# Digital.net
KiCad netlist of a schematic drawn in Altium Designer
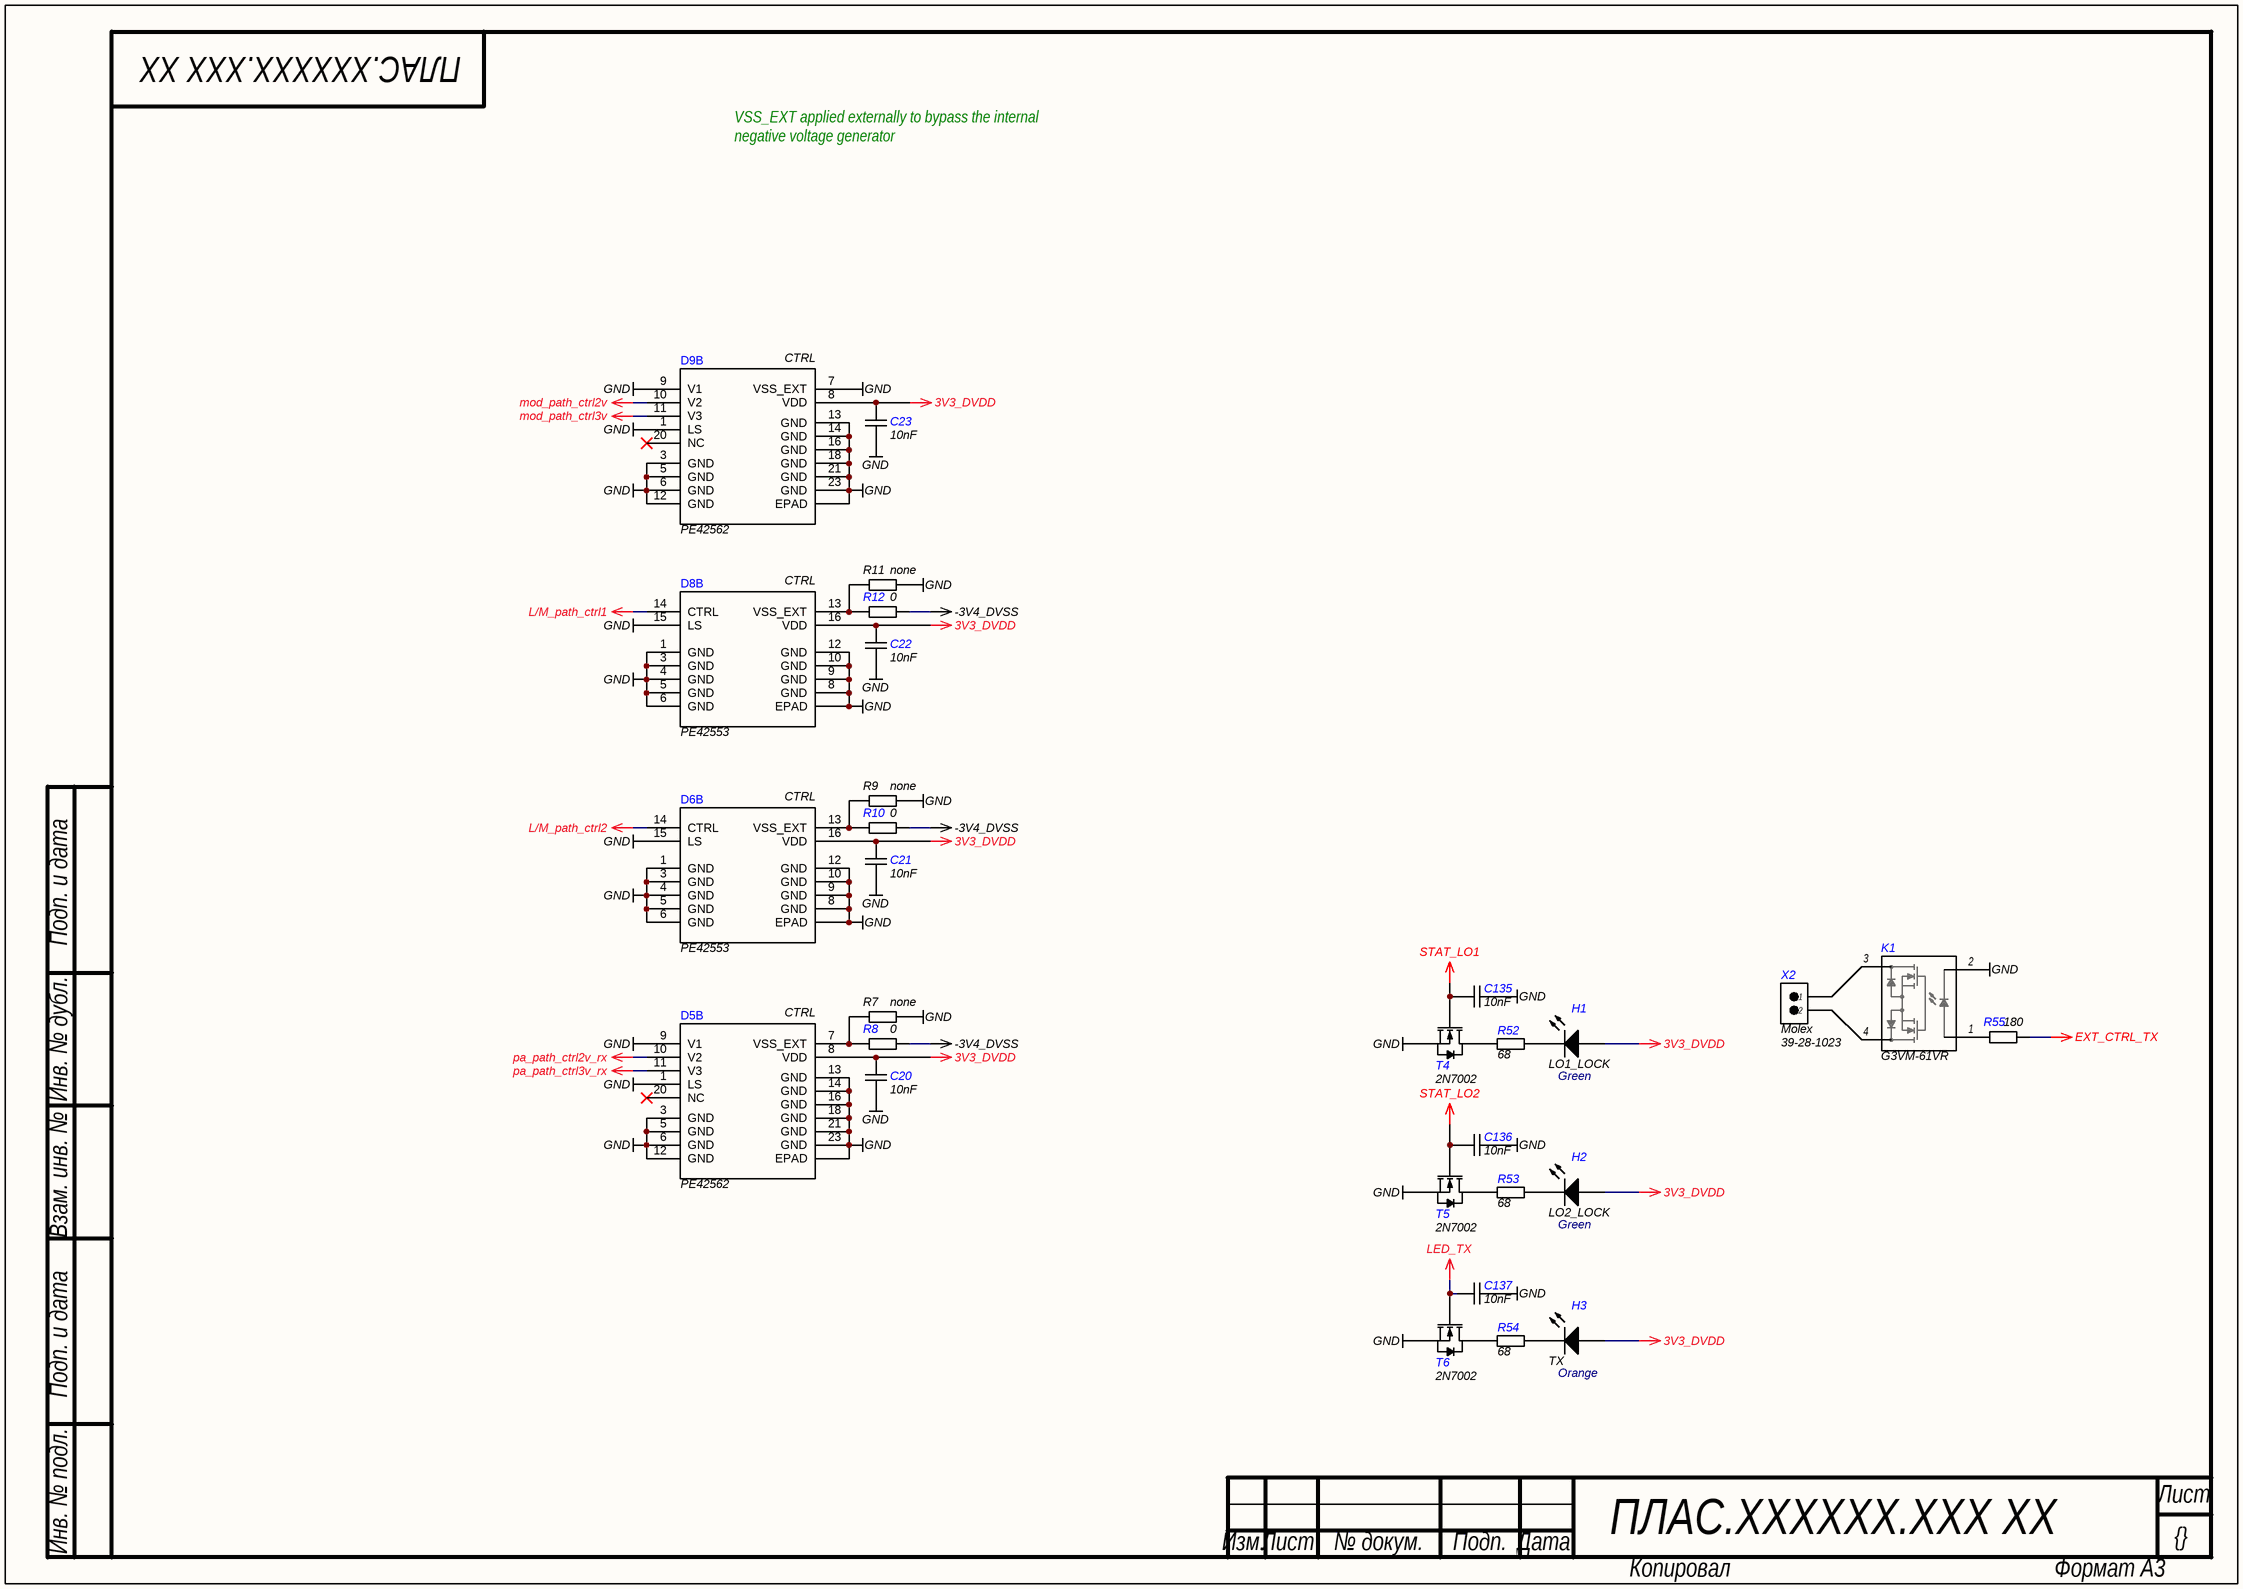
[diagram p0: Digital.SchDoc]

(export (version "E")
  (design (tool "Eeschema 10.0.6"))
  (components
    (comp (ref "C20")
      (value "10nF")
      (footprint "C0402")
      (description "SMD Capacitor")
      (fields (field (name "MANUFACTURER") "Murata") (field (name "TOLERANCE") "10%"))
      (libsource (lib "Kintex_SDR") (part "CAP"))
    )
    (comp (ref "C21")
      (value "10nF")
      (footprint "C0402")
      (description "SMD Capacitor")
      (fields (field (name "MANUFACTURER") "Murata") (field (name "TOLERANCE") "10%"))
      (libsource (lib "Kintex_SDR") (part "CAP"))
    )
    (comp (ref "C22")
      (value "10nF")
      (footprint "C0402")
      (description "SMD Capacitor")
      (fields (field (name "MANUFACTURER") "Murata") (field (name "TOLERANCE") "10%"))
      (libsource (lib "Kintex_SDR") (part "CAP"))
    )
    (comp (ref "C23")
      (value "10nF")
      (footprint "C0402")
      (description "SMD Capacitor")
      (fields (field (name "MANUFACTURER") "Murata") (field (name "TOLERANCE") "10%"))
      (libsource (lib "Kintex_SDR") (part "CAP"))
    )
    (comp (ref "C135")
      (value "10nF")
      (footprint "C0402")
      (description "SMD Capacitor")
      (fields (field (name "MANUFACTURER") "Murata") (field (name "TOLERANCE") "10%"))
      (libsource (lib "Kintex_SDR") (part "CAP"))
    )
    (comp (ref "C136")
      (value "10nF")
      (footprint "C0402")
      (description "SMD Capacitor")
      (fields (field (name "MANUFACTURER") "Murata") (field (name "TOLERANCE") "10%"))
      (libsource (lib "Kintex_SDR") (part "CAP"))
    )
    (comp (ref "C137")
      (value "10nF")
      (footprint "C0402")
      (description "SMD Capacitor")
      (fields (field (name "MANUFACTURER") "Murata") (field (name "TOLERANCE") "10%"))
      (libsource (lib "Kintex_SDR") (part "CAP"))
    )
    (comp (ref "D5")
      (value "PE42562")
      (footprint "QFN-24")
      (description "The PE42582 is a HaRP™ technology-enhanced absorptive SP6T RF switch")
      (fields (field (name "MANUFACTURER") "Peregrine Technical Solutions"))
      (libsource (lib "DBLib") (part "PE42562"))
    )
    (comp (ref "D6")
      (value "PE42553")
      (footprint "QFN-16")
      (description "HaRPTM technology-enhanced absorptive SPDT")
      (fields (field (name "MANUFACTURER") "Peregrine Technical Solutions"))
      (libsource (lib "DBLib") (part "PE42553"))
    )
    (comp (ref "D8")
      (value "PE42553")
      (footprint "QFN-16")
      (description "HaRPTM technology-enhanced absorptive SPDT")
      (fields (field (name "MANUFACTURER") "Peregrine Technical Solutions"))
      (libsource (lib "DBLib") (part "PE42553"))
    )
    (comp (ref "D9")
      (value "PE42562")
      (footprint "QFN-24")
      (description "The PE42582 is a HaRP™ technology-enhanced absorptive SP6T RF switch")
      (fields (field (name "MANUFACTURER") "Peregrine Technical Solutions"))
      (libsource (lib "DBLib") (part "PE42562"))
    )
    (comp (ref "H1")
      (value "LO1_LOCK")
      (footprint "LED_0805_Green")
      (description "CHIP LED LAMP")
      (fields (field (name "MANUFACTURER") "Kingbright") (field (name "COLOR") "Green"))
      (libsource (lib "DBLib") (part "LED"))
    )
    (comp (ref "H2")
      (value "LO2_LOCK")
      (footprint "LED_0805_Green")
      (description "CHIP LED LAMP")
      (fields (field (name "MANUFACTURER") "Kingbright") (field (name "COLOR") "Green"))
      (libsource (lib "DBLib") (part "LED"))
    )
    (comp (ref "H3")
      (value "TX")
      (footprint "LED_0805_Green")
      (description "CHIP LED LAMP")
      (fields (field (name "MANUFACTURER") "Kingbright") (field (name "COLOR") "Orange"))
      (libsource (lib "DBLib") (part "LED"))
    )
    (comp (ref "K1")
      (value "G3VM-61VR")
      (footprint "DBLib:G3VM-61")
      (description "MOS FET Relay")
      (fields (field (name "VOLTAGE") "60V") (field (name "MANUFACTURER") "Omron"))
      (libsource (lib "DBLib") (part "G3VM-61GR1"))
    )
    (comp (ref "R7")
      (value "none")
      (footprint "R0603")
      (description "SMD Resistor")
      (fields (field (name "POWER") "0.1 Wt") (field (name "TOLERANCE") "1%"))
      (libsource (lib "Kintex_SDR") (part "RES"))
    )
    (comp (ref "R8")
      (value "0")
      (footprint "R0603")
      (description "SMD Resistor")
      (fields (field (name "POWER") "0.1 Wt") (field (name "TOLERANCE") "1%"))
      (libsource (lib "") (part "RES_1"))
    )
    (comp (ref "R9")
      (value "none")
      (footprint "R0603")
      (description "SMD Resistor")
      (fields (field (name "POWER") "0.1 Wt") (field (name "TOLERANCE") "1%"))
      (libsource (lib "Kintex_SDR") (part "RES"))
    )
    (comp (ref "R10")
      (value "0")
      (footprint "R0603")
      (description "SMD Resistor")
      (fields (field (name "POWER") "0.1 Wt") (field (name "TOLERANCE") "1%"))
      (libsource (lib "") (part "RES_1"))
    )
    (comp (ref "R11")
      (value "none")
      (footprint "R0603")
      (description "SMD Resistor")
      (fields (field (name "POWER") "0.1 Wt") (field (name "TOLERANCE") "1%"))
      (libsource (lib "Kintex_SDR") (part "RES"))
    )
    (comp (ref "R12")
      (value "0")
      (footprint "R0603")
      (description "SMD Resistor")
      (fields (field (name "POWER") "0.1 Wt") (field (name "TOLERANCE") "1%"))
      (libsource (lib "") (part "RES_1"))
    )
    (comp (ref "R52")
      (value "68")
      (footprint "R0402")
      (description "SMD Resistor")
      (fields (field (name "POWER") "0.062 Wt") (field (name "TOLERANCE") "5%"))
      (libsource (lib "Kintex_SDR") (part "RES"))
    )
    (comp (ref "R53")
      (value "68")
      (footprint "R0402")
      (description "SMD Resistor")
      (fields (field (name "POWER") "0.062 Wt") (field (name "TOLERANCE") "5%"))
      (libsource (lib "Kintex_SDR") (part "RES"))
    )
    (comp (ref "R54")
      (value "68")
      (footprint "R0402")
      (description "SMD Resistor")
      (fields (field (name "POWER") "0.062 Wt") (field (name "TOLERANCE") "5%"))
      (libsource (lib "Kintex_SDR") (part "RES"))
    )
    (comp (ref "R55")
      (value "180")
      (footprint "R0402")
      (description "SMD Resistor")
      (fields (field (name "POWER") "0.063 Wt") (field (name "TOLERANCE") "1%"))
      (libsource (lib "Kintex_SDR") (part "RES"))
    )
    (comp (ref "T4")
      (value "2N7002")
      (footprint "SOT-23")
      (description "N-Channel MOSFET 2N7002")
      (fields (field (name "VOLTAGE") "60V"))
      (libsource (lib "Kintex_SDR") (part "2N7002"))
    )
    (comp (ref "T5")
      (value "2N7002")
      (footprint "SOT-23")
      (description "N-Channel MOSFET 2N7002")
      (fields (field (name "VOLTAGE") "60V"))
      (libsource (lib "Kintex_SDR") (part "2N7002"))
    )
    (comp (ref "T6")
      (value "2N7002")
      (footprint "SOT-23")
      (description "N-Channel MOSFET 2N7002")
      (fields (field (name "VOLTAGE") "60V"))
      (libsource (lib "Kintex_SDR") (part "2N7002"))
    )
    (comp (ref "X2")
      (value "Mini-Fit Jr. Vertical Header")
      (footprint "DBLib:Mini-Fit Jr. Vertical Header")
      (description "4.20mm Pitch, Dual Row, 2 Circuits, without Snap-in Plastic Peg PCB Lock")
      (fields (field (name "MANUFACTURER") "Molex") (field (name "P/N") "39-28-1023"))
      (libsource (lib "DBLib") (part "Mini-Fit Jr. Vertical Header"))
    )
  )
  (nets
    (net (code "1") (name "-3V4_DVSS") (class "Default")
      (node (ref "R10") (pin "1") (pinfunction "1_1") (pintype "passive"))
      (node (ref "R12") (pin "1") (pinfunction "1_1") (pintype "passive"))
      (node (ref "R8") (pin "1") (pinfunction "1_1") (pintype "passive"))
    )
    (net (code "2") (name "3V3_DVDD") (class "Default")
      (node (ref "C20") (pin "1") (pinfunction "1_1") (pintype "passive"))
      (node (ref "C21") (pin "1") (pinfunction "1_1") (pintype "passive"))
      (node (ref "C22") (pin "1") (pinfunction "1_1") (pintype "passive"))
      (node (ref "C23") (pin "1") (pinfunction "1_1") (pintype "passive"))
      (node (ref "D5") (pin "8") (pinfunction "VDD_8") (pintype "passive"))
      (node (ref "D6") (pin "16") (pinfunction "VDD_16") (pintype "passive"))
      (node (ref "D8") (pin "16") (pinfunction "VDD_16") (pintype "passive"))
      (node (ref "D9") (pin "8") (pinfunction "VDD_8") (pintype "passive"))
      (node (ref "H1") (pin "2") (pinfunction "A_2") (pintype "passive"))
      (node (ref "H2") (pin "2") (pinfunction "A_2") (pintype "passive"))
      (node (ref "H3") (pin "2") (pinfunction "A_2") (pintype "passive"))
    )
    (net (code "3") (name "EXT_CTRL_TX") (class "Default")
      (node (ref "R55") (pin "2") (pinfunction "2_2") (pintype "passive"))
    )
    (net (code "4") (name "GND") (class "Default")
      (node (ref "C135") (pin "2") (pinfunction "2_2") (pintype "passive"))
      (node (ref "C136") (pin "2") (pinfunction "2_2") (pintype "passive"))
      (node (ref "C137") (pin "2") (pinfunction "2_2") (pintype "passive"))
      (node (ref "C20") (pin "2") (pinfunction "2_2") (pintype "passive"))
      (node (ref "C21") (pin "2") (pinfunction "2_2") (pintype "passive"))
      (node (ref "C22") (pin "2") (pinfunction "2_2") (pintype "passive"))
      (node (ref "C23") (pin "2") (pinfunction "2_2") (pintype "passive"))
      (node (ref "D5") (pin "1") (pinfunction "LS_1") (pintype "passive"))
      (node (ref "D5") (pin "12") (pinfunction "GND_12") (pintype "passive"))
      (node (ref "D5") (pin "13") (pinfunction "GND_13") (pintype "passive"))
      (node (ref "D5") (pin "14") (pinfunction "GND_14") (pintype "passive"))
      (node (ref "D5") (pin "16") (pinfunction "GND_16") (pintype "passive"))
      (node (ref "D5") (pin "18") (pinfunction "GND_18") (pintype "passive"))
      (node (ref "D5") (pin "21") (pinfunction "GND_21") (pintype "passive"))
      (node (ref "D5") (pin "23") (pinfunction "GND_23") (pintype "passive"))
      (node (ref "D5") (pin "25") (pinfunction "EPAD_25") (pintype "passive"))
      (node (ref "D5") (pin "3") (pinfunction "GND_3") (pintype "passive"))
      (node (ref "D5") (pin "5") (pinfunction "GND_5") (pintype "passive"))
      (node (ref "D5") (pin "6") (pinfunction "GND_6") (pintype "passive"))
      (node (ref "D5") (pin "9") (pinfunction "V1_9") (pintype "passive"))
      (node (ref "D6") (pin "1") (pinfunction "GND_1") (pintype "passive"))
      (node (ref "D6") (pin "10") (pinfunction "GND_10") (pintype "passive"))
      (node (ref "D6") (pin "12") (pinfunction "GND_12") (pintype "passive"))
      (node (ref "D6") (pin "15") (pinfunction "LS_15") (pintype "passive"))
      (node (ref "D6") (pin "17") (pinfunction "EPAD_17") (pintype "passive"))
      (node (ref "D6") (pin "3") (pinfunction "GND_3") (pintype "passive"))
      (node (ref "D6") (pin "4") (pinfunction "GND_4") (pintype "passive"))
      (node (ref "D6") (pin "5") (pinfunction "GND_5") (pintype "passive"))
      (node (ref "D6") (pin "6") (pinfunction "GND_6") (pintype "passive"))
      (node (ref "D6") (pin "8") (pinfunction "GND_8") (pintype "passive"))
      (node (ref "D6") (pin "9") (pinfunction "GND_9") (pintype "passive"))
      (node (ref "D8") (pin "1") (pinfunction "GND_1") (pintype "passive"))
      (node (ref "D8") (pin "10") (pinfunction "GND_10") (pintype "passive"))
      (node (ref "D8") (pin "12") (pinfunction "GND_12") (pintype "passive"))
      (node (ref "D8") (pin "15") (pinfunction "LS_15") (pintype "passive"))
      (node (ref "D8") (pin "17") (pinfunction "EPAD_17") (pintype "passive"))
      (node (ref "D8") (pin "3") (pinfunction "GND_3") (pintype "passive"))
      (node (ref "D8") (pin "4") (pinfunction "GND_4") (pintype "passive"))
      (node (ref "D8") (pin "5") (pinfunction "GND_5") (pintype "passive"))
      (node (ref "D8") (pin "6") (pinfunction "GND_6") (pintype "passive"))
      (node (ref "D8") (pin "8") (pinfunction "GND_8") (pintype "passive"))
      (node (ref "D8") (pin "9") (pinfunction "GND_9") (pintype "passive"))
      (node (ref "D9") (pin "1") (pinfunction "LS_1") (pintype "passive"))
      (node (ref "D9") (pin "12") (pinfunction "GND_12") (pintype "passive"))
      (node (ref "D9") (pin "13") (pinfunction "GND_13") (pintype "passive"))
      (node (ref "D9") (pin "14") (pinfunction "GND_14") (pintype "passive"))
      (node (ref "D9") (pin "16") (pinfunction "GND_16") (pintype "passive"))
      (node (ref "D9") (pin "18") (pinfunction "GND_18") (pintype "passive"))
      (node (ref "D9") (pin "21") (pinfunction "GND_21") (pintype "passive"))
      (node (ref "D9") (pin "23") (pinfunction "GND_23") (pintype "passive"))
      (node (ref "D9") (pin "25") (pinfunction "EPAD_25") (pintype "passive"))
      (node (ref "D9") (pin "3") (pinfunction "GND_3") (pintype "passive"))
      (node (ref "D9") (pin "5") (pinfunction "GND_5") (pintype "passive"))
      (node (ref "D9") (pin "6") (pinfunction "GND_6") (pintype "passive"))
      (node (ref "D9") (pin "7") (pinfunction "VSS_EXT_7") (pintype "passive"))
      (node (ref "D9") (pin "9") (pinfunction "V1_9") (pintype "passive"))
      (node (ref "K1") (pin "2") (pinfunction "2_2") (pintype "passive"))
      (node (ref "R11") (pin "2") (pinfunction "2_2") (pintype "passive"))
      (node (ref "R7") (pin "2") (pinfunction "2_2") (pintype "passive"))
      (node (ref "R9") (pin "2") (pinfunction "2_2") (pintype "passive"))
      (node (ref "T4") (pin "2") (pinfunction "S_2") (pintype "passive"))
      (node (ref "T5") (pin "2") (pinfunction "S_2") (pintype "passive"))
      (node (ref "T6") (pin "2") (pinfunction "S_2") (pintype "passive"))
    )
    (net (code "5") (name "LED_TX") (class "Default")
      (node (ref "C137") (pin "1") (pinfunction "1_1") (pintype "passive"))
      (node (ref "T6") (pin "1") (pinfunction "G_1") (pintype "passive"))
    )
    (net (code "6") (name "L{slash}M_path_ctrl1") (class "Default")
      (node (ref "D8") (pin "14") (pinfunction "CTRL_14") (pintype "passive"))
    )
    (net (code "7") (name "L{slash}M_path_ctrl2") (class "Default")
      (node (ref "D6") (pin "14") (pinfunction "CTRL_14") (pintype "passive"))
    )
    (net (code "8") (name "Net-(D5B-VSS_EXT)") (class "Default")
      (node (ref "D5") (pin "7") (pinfunction "VSS_EXT_7") (pintype "passive"))
      (node (ref "R7") (pin "1") (pinfunction "1_1") (pintype "passive"))
      (node (ref "R8") (pin "2") (pinfunction "2_2") (pintype "passive"))
    )
    (net (code "9") (name "Net-(D6B-VSS_EXT)") (class "Default")
      (node (ref "D6") (pin "13") (pinfunction "VSS_EXT_13") (pintype "passive"))
      (node (ref "R10") (pin "2") (pinfunction "2_2") (pintype "passive"))
      (node (ref "R9") (pin "1") (pinfunction "1_1") (pintype "passive"))
    )
    (net (code "10") (name "Net-(D8B-VSS_EXT)") (class "Default")
      (node (ref "D8") (pin "13") (pinfunction "VSS_EXT_13") (pintype "passive"))
      (node (ref "R11") (pin "1") (pinfunction "1_1") (pintype "passive"))
      (node (ref "R12") (pin "2") (pinfunction "2_2") (pintype "passive"))
    )
    (net (code "11") (name "Net-(H1-K)") (class "Default")
      (node (ref "H1") (pin "1") (pinfunction "K_1") (pintype "passive"))
      (node (ref "R52") (pin "2") (pinfunction "2_2") (pintype "passive"))
    )
    (net (code "12") (name "Net-(H2-K)") (class "Default")
      (node (ref "H2") (pin "1") (pinfunction "K_1") (pintype "passive"))
      (node (ref "R53") (pin "2") (pinfunction "2_2") (pintype "passive"))
    )
    (net (code "13") (name "Net-(H3-K)") (class "Default")
      (node (ref "H3") (pin "1") (pinfunction "K_1") (pintype "passive"))
      (node (ref "R54") (pin "2") (pinfunction "2_2") (pintype "passive"))
    )
    (net (code "14") (name "Net-(K1-Pad1)") (class "Default")
      (node (ref "K1") (pin "1") (pinfunction "1_1") (pintype "passive"))
      (node (ref "R55") (pin "1") (pinfunction "1_1") (pintype "passive"))
    )
    (net (code "15") (name "Net-(K1-Pad3)") (class "Default")
      (node (ref "K1") (pin "3") (pinfunction "3_3") (pintype "passive"))
      (node (ref "X2") (pin "1") (pinfunction "1_1") (pintype "passive"))
    )
    (net (code "16") (name "Net-(K1-Pad4)") (class "Default")
      (node (ref "K1") (pin "4") (pinfunction "4_4") (pintype "passive"))
      (node (ref "X2") (pin "2") (pinfunction "2_2") (pintype "passive"))
    )
    (net (code "17") (name "Net-(T4-D)") (class "Default")
      (node (ref "R52") (pin "1") (pinfunction "1_1") (pintype "passive"))
      (node (ref "T4") (pin "3") (pinfunction "D_3") (pintype "passive"))
    )
    (net (code "18") (name "Net-(T5-D)") (class "Default")
      (node (ref "R53") (pin "1") (pinfunction "1_1") (pintype "passive"))
      (node (ref "T5") (pin "3") (pinfunction "D_3") (pintype "passive"))
    )
    (net (code "19") (name "Net-(T6-D)") (class "Default")
      (node (ref "R54") (pin "1") (pinfunction "1_1") (pintype "passive"))
      (node (ref "T6") (pin "3") (pinfunction "D_3") (pintype "passive"))
    )
    (net (code "20") (name "STAT_LO1") (class "Default")
      (node (ref "C135") (pin "1") (pinfunction "1_1") (pintype "passive"))
      (node (ref "T4") (pin "1") (pinfunction "G_1") (pintype "passive"))
    )
    (net (code "21") (name "STAT_LO2") (class "Default")
      (node (ref "C136") (pin "1") (pinfunction "1_1") (pintype "passive"))
      (node (ref "T5") (pin "1") (pinfunction "G_1") (pintype "passive"))
    )
    (net (code "22") (name "mod_path_ctrl2v") (class "Default")
      (node (ref "D9") (pin "10") (pinfunction "V2_10") (pintype "passive"))
    )
    (net (code "23") (name "mod_path_ctrl3v") (class "Default")
      (node (ref "D9") (pin "11") (pinfunction "V3_11") (pintype "passive"))
    )
    (net (code "24") (name "pa_path_ctrl2v_rx") (class "Default")
      (node (ref "D5") (pin "10") (pinfunction "V2_10") (pintype "passive"))
    )
    (net (code "25") (name "pa_path_ctrl3v_rx") (class "Default")
      (node (ref "D5") (pin "11") (pinfunction "V3_11") (pintype "passive"))
    )
    (net (code "26") (name "unconnected-(D5B-NC-Pad20)") (class "Default")
      (node (ref "D5") (pin "20") (pinfunction "NC_20") (pintype "passive+no_connect"))
    )
    (net (code "27") (name "unconnected-(D9B-NC-Pad20)") (class "Default")
      (node (ref "D9") (pin "20") (pinfunction "NC_20") (pintype "passive+no_connect"))
    )
  )
)
